# TMC2208_OTP.net
KiCad netlist of a schematic drawn in EAGLE
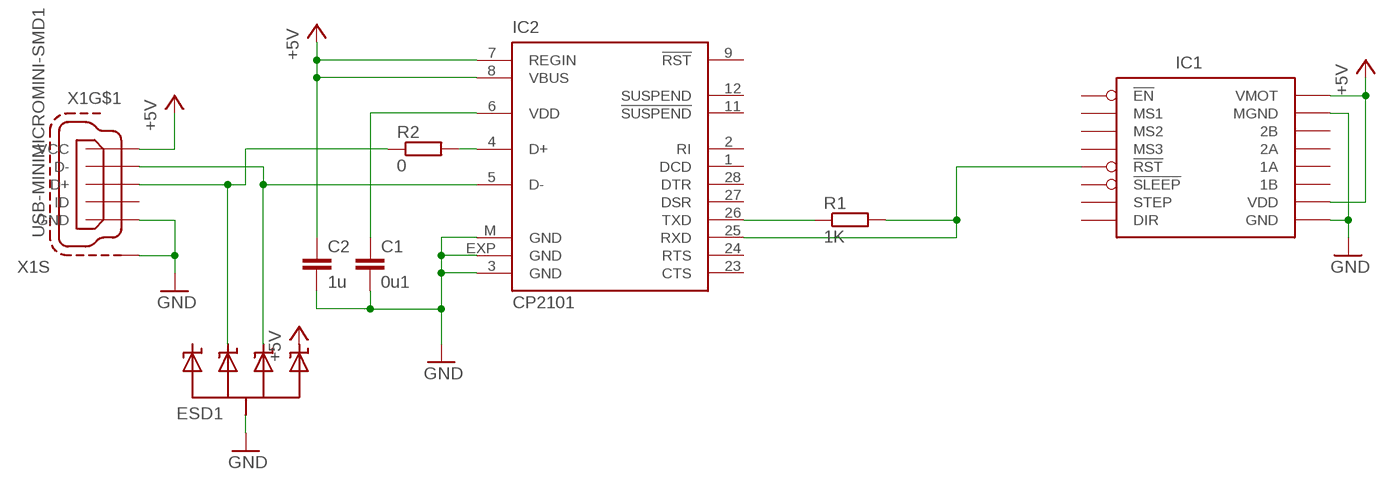
[diagram p0: schematic, sheet 1]

(export (version "E")
  (design (tool "Eeschema 10.0.6"))
  (components
    (comp (ref "C1")
      (value "0u1")
      (footprint "eagle-import:C0805")
      (libsource (lib "eagle-import") (part "CAP_0805"))
    )
    (comp (ref "C2")
      (value "1u")
      (footprint "eagle-import:C0805")
      (libsource (lib "eagle-import") (part "CAP_0805"))
    )
    (comp (ref "ESD1")
      (value "ESDAXXSC5")
      (footprint "eagle-import:SOT23-5L")
      (libsource (lib "eagle-import") (part "ESDAXXSC5"))
    )
    (comp (ref "IC1")
      (value "STEP-DRV")
      (footprint "eagle-import:DRV-BRK")
      (libsource (lib "eagle-import") (part "STEP-DRV"))
    )
    (comp (ref "IC2")
      (value "CP2101")
      (footprint "eagle-import:MLP28")
      (fields (field (name "MF") "FARNELL") (field (name "MPN") "CP2102-GM"))
      (libsource (lib "eagle-import") (part "CP2101"))
    )
    (comp (ref "R1")
      (value "1K")
      (footprint "eagle-import:R0805")
      (libsource (lib "eagle-import") (part "R_0805"))
    )
    (comp (ref "R2")
      (value "0")
      (footprint "eagle-import:R0805")
      (libsource (lib "eagle-import") (part "R_0805"))
    )
    (comp (ref "X1")
      (value "USB-MINIMICROMINI-SMD1")
      (footprint "eagle-import:32005-201")
      (libsource (lib "eagle-import") (part "USB-MINIMICROMINI-SMD1"))
    )
  )
  (nets
    (net (code "1") (name "+5V") (class "Default")
      (node (ref "C2") (pin "1") (pinfunction "1_1") (pintype "passive"))
      (node (ref "ESD1") (pin "5") (pinfunction "C4_5") (pintype "passive"))
      (node (ref "IC1") (pin "P$10") (pinfunction "VDD_P$10") (pintype "bidirectional"))
      (node (ref "IC1") (pin "P$16") (pinfunction "VMOT_P$16") (pintype "bidirectional"))
      (node (ref "IC2") (pin "7") (pinfunction "REGIN_7") (pintype "passive"))
      (node (ref "IC2") (pin "8") (pinfunction "VBUS_8") (pintype "input"))
      (node (ref "X1") (pin "1") (pinfunction "VCC_1") (pintype "passive"))
    )
    (net (code "2") (name "GND") (class "Default")
      (node (ref "C1") (pin "2") (pinfunction "2_2") (pintype "passive"))
      (node (ref "C2") (pin "2") (pinfunction "2_2") (pintype "passive"))
      (node (ref "ESD1") (pin "2") (pinfunction "A_2") (pintype "passive"))
      (node (ref "IC1") (pin "P$15") (pinfunction "MGND_P$15") (pintype "bidirectional"))
      (node (ref "IC1") (pin "P$9") (pinfunction "GND_P$9") (pintype "bidirectional"))
      (node (ref "IC2") (pin "3") (pinfunction "GND_3") (pintype "power_in"))
      (node (ref "IC2") (pin "EXP") (pinfunction "GND_EXP") (pintype "power_in"))
      (node (ref "IC2") (pin "M") (pinfunction "GND_M") (pintype "power_in"))
      (node (ref "X1") (pin "5") (pinfunction "GND_5") (pintype "passive"))
      (node (ref "X1") (pin "M1") (pinfunction "S1_M1") (pintype "passive"))
      (node (ref "X1") (pin "M2") (pinfunction "S1_M2") (pintype "passive"))
      (node (ref "X1") (pin "M3") (pinfunction "S1_M3") (pintype "passive"))
      (node (ref "X1") (pin "M4") (pinfunction "S1_M4") (pintype "passive"))
    )
    (net (code "3") (name "Net-(ESD1-C2)") (class "Default")
      (node (ref "ESD1") (pin "3") (pinfunction "C2_3") (pintype "passive"))
      (node (ref "R2") (pin "1") (pinfunction "1_1") (pintype "passive"))
      (node (ref "X1") (pin "3") (pinfunction "D+_3") (pintype "passive"))
    )
    (net (code "4") (name "Net-(ESD1-C3)") (class "Default")
      (node (ref "ESD1") (pin "4") (pinfunction "C3_4") (pintype "passive"))
      (node (ref "IC2") (pin "5") (pinfunction "D-_5") (pintype "bidirectional"))
      (node (ref "X1") (pin "2") (pinfunction "D-_2") (pintype "passive"))
    )
    (net (code "5") (name "Net-(IC1-~{RST})") (class "Default")
      (node (ref "IC1") (pin "P$5") (pinfunction "~{RST}_P$5") (pintype "bidirectional"))
      (node (ref "IC2") (pin "25") (pinfunction "RXD_25") (pintype "input"))
      (node (ref "R1") (pin "2") (pinfunction "2_2") (pintype "passive"))
    )
    (net (code "6") (name "Net-(IC2-D+)") (class "Default")
      (node (ref "IC2") (pin "4") (pinfunction "D+_4") (pintype "bidirectional"))
      (node (ref "R2") (pin "2") (pinfunction "2_2") (pintype "passive"))
    )
    (net (code "7") (name "Net-(IC2-TXD)") (class "Default")
      (node (ref "IC2") (pin "26") (pinfunction "TXD_26") (pintype "output"))
      (node (ref "R1") (pin "1") (pinfunction "1_1") (pintype "passive"))
    )
    (net (code "8") (name "Net-(IC2-VDD)") (class "Default")
      (node (ref "C1") (pin "1") (pinfunction "1_1") (pintype "passive"))
      (node (ref "IC2") (pin "6") (pinfunction "VDD_6") (pintype "power_in"))
    )
    (net (code "9") (name "unconnected-(ESD1-C1-Pad1)") (class "Default")
      (node (ref "ESD1") (pin "1") (pinfunction "C1_1") (pintype "passive"))
    )
    (net (code "10") (name "unconnected-(IC1-1A-PadP$12)") (class "Default")
      (node (ref "IC1") (pin "P$12") (pinfunction "1A_P$12") (pintype "bidirectional"))
    )
    (net (code "11") (name "unconnected-(IC1-1B-PadP$11)") (class "Default")
      (node (ref "IC1") (pin "P$11") (pinfunction "1B_P$11") (pintype "bidirectional"))
    )
    (net (code "12") (name "unconnected-(IC1-2A-PadP$13)") (class "Default")
      (node (ref "IC1") (pin "P$13") (pinfunction "2A_P$13") (pintype "bidirectional"))
    )
    (net (code "13") (name "unconnected-(IC1-2B-PadP$14)") (class "Default")
      (node (ref "IC1") (pin "P$14") (pinfunction "2B_P$14") (pintype "bidirectional"))
    )
    (net (code "14") (name "unconnected-(IC1-DIR-PadP$8)") (class "Default")
      (node (ref "IC1") (pin "P$8") (pinfunction "DIR_P$8") (pintype "bidirectional"))
    )
    (net (code "15") (name "unconnected-(IC1-MS1-PadP$2)") (class "Default")
      (node (ref "IC1") (pin "P$2") (pinfunction "MS1_P$2") (pintype "bidirectional"))
    )
    (net (code "16") (name "unconnected-(IC1-MS2-PadP$3)") (class "Default")
      (node (ref "IC1") (pin "P$3") (pinfunction "MS2_P$3") (pintype "bidirectional"))
    )
    (net (code "17") (name "unconnected-(IC1-MS3-PadP$4)") (class "Default")
      (node (ref "IC1") (pin "P$4") (pinfunction "MS3_P$4") (pintype "bidirectional"))
    )
    (net (code "18") (name "unconnected-(IC1-STEP-PadP$7)") (class "Default")
      (node (ref "IC1") (pin "P$7") (pinfunction "STEP_P$7") (pintype "bidirectional"))
    )
    (net (code "19") (name "unconnected-(IC1-~{EN}-PadP$1)") (class "Default")
      (node (ref "IC1") (pin "P$1") (pinfunction "~{EN}_P$1") (pintype "bidirectional"))
    )
    (net (code "20") (name "unconnected-(IC1-~{SLEEP}-PadP$6)") (class "Default")
      (node (ref "IC1") (pin "P$6") (pinfunction "~{SLEEP}_P$6") (pintype "bidirectional"))
    )
    (net (code "21") (name "unconnected-(IC2-CTS-Pad23)") (class "Default")
      (node (ref "IC2") (pin "23") (pinfunction "CTS_23") (pintype "input"))
    )
    (net (code "22") (name "unconnected-(IC2-DCD-Pad1)") (class "Default")
      (node (ref "IC2") (pin "1") (pinfunction "DCD_1") (pintype "input"))
    )
    (net (code "23") (name "unconnected-(IC2-DSR-Pad27)") (class "Default")
      (node (ref "IC2") (pin "27") (pinfunction "DSR_27") (pintype "input"))
    )
    (net (code "24") (name "unconnected-(IC2-DTR-Pad28)") (class "Default")
      (node (ref "IC2") (pin "28") (pinfunction "DTR_28") (pintype "output"))
    )
    (net (code "25") (name "unconnected-(IC2-RI-Pad2)") (class "Default")
      (node (ref "IC2") (pin "2") (pinfunction "RI_2") (pintype "input"))
    )
    (net (code "26") (name "unconnected-(IC2-RTS-Pad24)") (class "Default")
      (node (ref "IC2") (pin "24") (pinfunction "RTS_24") (pintype "output"))
    )
    (net (code "27") (name "unconnected-(IC2-SUSPEND-Pad12)") (class "Default")
      (node (ref "IC2") (pin "12") (pinfunction "SUSPEND_12") (pintype "output"))
    )
    (net (code "28") (name "unconnected-(IC2-~{RST}-Pad9)") (class "Default")
      (node (ref "IC2") (pin "9") (pinfunction "~{RST}_9") (pintype "bidirectional"))
    )
    (net (code "29") (name "unconnected-(IC2-~{SUSPEND}-Pad11)") (class "Default")
      (node (ref "IC2") (pin "11") (pinfunction "~{SUSPEND}_11") (pintype "output"))
    )
    (net (code "30") (name "unconnected-(X1A-ID-Pad4)") (class "Default")
      (node (ref "X1") (pin "4") (pinfunction "ID_4") (pintype "passive"))
    )
  )
)
